# DigitalOutput.net
KiCad netlist of a schematic drawn in Altium Designer
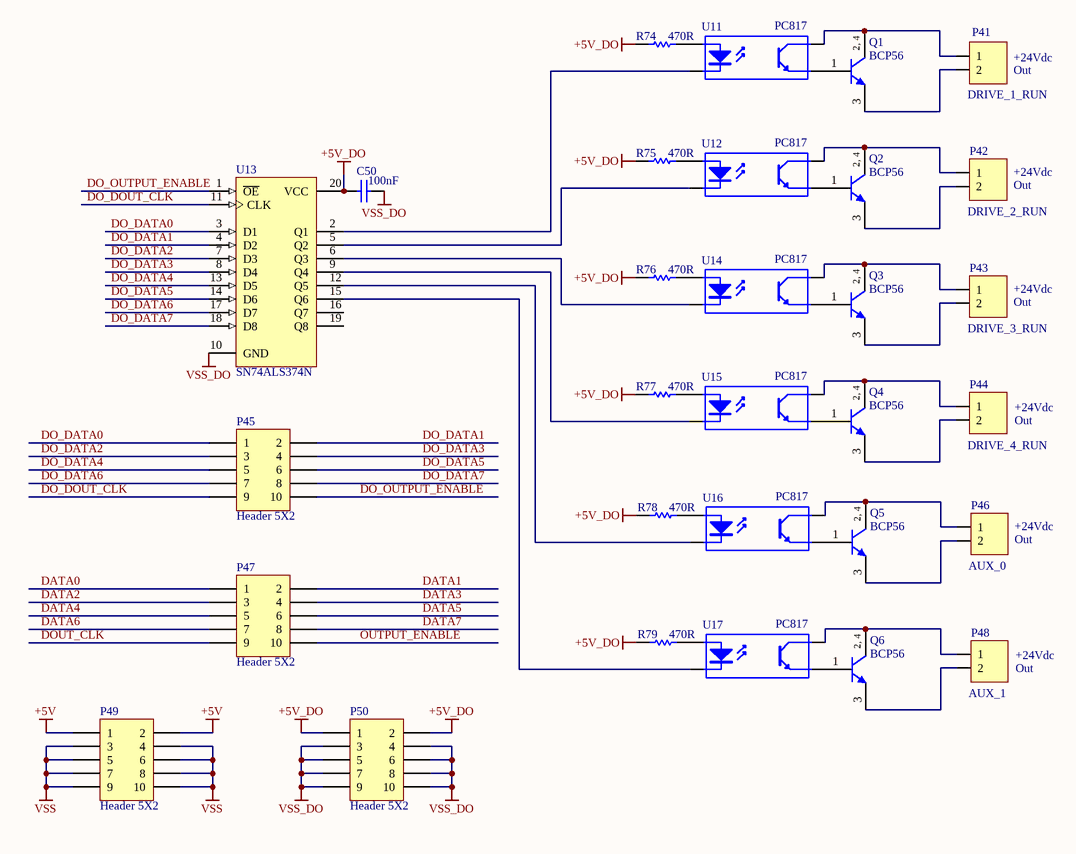
[diagram p0: DigitalOutput.SchDoc]

(export (version "E")
  (design (tool "Eeschema 10.0.6"))
  (components
    (comp (ref "C50")
      (value "100nF")
      (footprint "1206")
      (description "Ceramic Chip Capacitor - Standard")
      (fields (field (name "PUBLISHER") "Altium Limited"))
      (libsource (lib "KEMET Chip Capacitor") (part "C1206"))
    )
    (comp (ref "P41")
      (value "DRIVE_1_RUN")
      (footprint "TERMINAL BLOK 2")
      (description "Terminal blok 2")
      (libsource (lib "") (part "Terminal blok 2 pina_1"))
    )
    (comp (ref "P42")
      (value "DRIVE_2_RUN")
      (footprint "TERMINAL BLOK 2")
      (description "Terminal blok 2")
      (libsource (lib "TERMINAL_CONNECOR_2") (part "Terminal blok 2 pina"))
    )
    (comp (ref "P43")
      (value "DRIVE_3_RUN")
      (footprint "TERMINAL BLOK 2")
      (description "Terminal blok 2")
      (libsource (lib "") (part "Terminal blok 2 pina_2"))
    )
    (comp (ref "P44")
      (value "DRIVE_4_RUN")
      (footprint "TERMINAL BLOK 2")
      (description "Terminal blok 2")
      (libsource (lib "") (part "Terminal blok 2 pina_1"))
    )
    (comp (ref "P45")
      (value "Header 5X2")
      (footprint "HDR2X5")
      (description "Header, 5-Pin, Dual row")
      (fields (field (name "PUBLISHER") "Altium Limited"))
      (libsource (lib "Miscellaneous Connectors") (part "Header 5X2"))
    )
    (comp (ref "P46")
      (value "AUX_0")
      (footprint "TERMINAL BLOK 2")
      (description "Terminal blok 2")
      (libsource (lib "") (part "Terminal blok 2 pina_1"))
    )
    (comp (ref "P47")
      (value "Header 5X2")
      (footprint "HDR2X5")
      (description "Header, 5-Pin, Dual row")
      (fields (field (name "PUBLISHER") "Altium Limited"))
      (libsource (lib "Miscellaneous Connectors") (part "Header 5X2"))
    )
    (comp (ref "P48")
      (value "AUX_1")
      (footprint "TERMINAL BLOK 2")
      (description "Terminal blok 2")
      (libsource (lib "TERMINAL_CONNECOR_2") (part "Terminal blok 2 pina"))
    )
    (comp (ref "P49")
      (value "Header 5X2")
      (footprint "HDR2X5")
      (description "Header, 5-Pin, Dual row")
      (fields (field (name "PUBLISHER") "Altium Limited"))
      (libsource (lib "Miscellaneous Connectors") (part "Header 5X2"))
    )
    (comp (ref "P50")
      (value "Header 5X2")
      (footprint "HDR2X5")
      (description "Header, 5-Pin, Dual row")
      (fields (field (name "PUBLISHER") "Altium Limited"))
      (libsource (lib "Miscellaneous Connectors") (part "Header 5X2"))
    )
    (comp (ref "Q1")
      (value "BCP56")
      (footprint "SOT223_N")
      (description "NPN Medium Power Transistor")
      (fields (field (name "PUBLISHER") "Altium Limited"))
      (libsource (lib "Philips Discrete BJT - Medium Power") (part "BCP56"))
    )
    (comp (ref "Q2")
      (value "BCP56")
      (footprint "SOT223_N")
      (description "NPN Medium Power Transistor")
      (fields (field (name "PUBLISHER") "Altium Limited"))
      (libsource (lib "Philips Discrete BJT - Medium Power") (part "BCP56"))
    )
    (comp (ref "Q3")
      (value "BCP56")
      (footprint "SOT223_N")
      (description "NPN Medium Power Transistor")
      (fields (field (name "PUBLISHER") "Altium Limited"))
      (libsource (lib "Philips Discrete BJT - Medium Power") (part "BCP56"))
    )
    (comp (ref "Q4")
      (value "BCP56")
      (footprint "SOT223_N")
      (description "NPN Medium Power Transistor")
      (fields (field (name "PUBLISHER") "Altium Limited"))
      (libsource (lib "Philips Discrete BJT - Medium Power") (part "BCP56"))
    )
    (comp (ref "Q5")
      (value "BCP56")
      (footprint "SOT223_N")
      (description "NPN Medium Power Transistor")
      (fields (field (name "PUBLISHER") "Altium Limited"))
      (libsource (lib "Philips Discrete BJT - Medium Power") (part "BCP56"))
    )
    (comp (ref "Q6")
      (value "BCP56")
      (footprint "SOT223_N")
      (description "NPN Medium Power Transistor")
      (fields (field (name "PUBLISHER") "Altium Limited"))
      (libsource (lib "Philips Discrete BJT - Medium Power") (part "BCP56"))
    )
    (comp (ref "R74")
      (value "470R")
      (footprint "ERA-0805")
      (fields (field (name "PUBLISHER") "Altium Limited"))
      (libsource (lib "Panasonic Resistor") (part "ERAS"))
    )
    (comp (ref "R75")
      (value "470R")
      (footprint "ERA-0805")
      (fields (field (name "PUBLISHER") "Altium Limited"))
      (libsource (lib "Panasonic Resistor") (part "ERAS"))
    )
    (comp (ref "R76")
      (value "470R")
      (footprint "ERA-0805")
      (fields (field (name "PUBLISHER") "Altium Limited"))
      (libsource (lib "Panasonic Resistor") (part "ERAS"))
    )
    (comp (ref "R77")
      (value "470R")
      (footprint "ERA-0805")
      (fields (field (name "PUBLISHER") "Altium Limited"))
      (libsource (lib "Panasonic Resistor") (part "ERAS"))
    )
    (comp (ref "R78")
      (value "470R")
      (footprint "ERA-0805")
      (fields (field (name "PUBLISHER") "Altium Limited"))
      (libsource (lib "Panasonic Resistor") (part "ERAS"))
    )
    (comp (ref "R79")
      (value "470R")
      (footprint "ERA-0805")
      (fields (field (name "PUBLISHER") "Altium Limited"))
      (libsource (lib "Panasonic Resistor") (part "ERAS"))
    )
    (comp (ref "U11")
      (value "PC817")
      (footprint "DIP-4")
      (description "4-Pin Phototransistor Optocoupler")
      (fields (field (name "PUBLISHER") "Altium Limited"))
      (libsource (lib "Miscellaneous Devices") (part "Optoisolator1"))
    )
    (comp (ref "U12")
      (value "PC817")
      (footprint "DIP-4")
      (description "4-Pin Phototransistor Optocoupler")
      (fields (field (name "PUBLISHER") "Altium Limited"))
      (libsource (lib "Miscellaneous Devices") (part "Optoisolator1"))
    )
    (comp (ref "U13")
      (value "SN74ALS374N")
      (footprint "N020D")
      (description "Octal D-Type Edge-Triggered Flip-Flop with 3-State Outputs")
      (fields (field (name "PUBLISHER") "Altium Limited"))
      (libsource (lib "TI Logic Flip-Flop") (part "SN74ALS374N"))
    )
    (comp (ref "U14")
      (value "PC817")
      (footprint "DIP-4")
      (description "4-Pin Phototransistor Optocoupler")
      (fields (field (name "PUBLISHER") "Altium Limited"))
      (libsource (lib "Miscellaneous Devices") (part "Optoisolator1"))
    )
    (comp (ref "U15")
      (value "PC817")
      (footprint "DIP-4")
      (description "4-Pin Phototransistor Optocoupler")
      (fields (field (name "PUBLISHER") "Altium Limited"))
      (libsource (lib "Miscellaneous Devices") (part "Optoisolator1"))
    )
    (comp (ref "U16")
      (value "PC817")
      (footprint "DIP-4")
      (description "4-Pin Phototransistor Optocoupler")
      (fields (field (name "PUBLISHER") "Altium Limited"))
      (libsource (lib "Miscellaneous Devices") (part "Optoisolator1"))
    )
    (comp (ref "U17")
      (value "PC817")
      (footprint "DIP-4")
      (description "4-Pin Phototransistor Optocoupler")
      (fields (field (name "PUBLISHER") "Altium Limited"))
      (libsource (lib "Miscellaneous Devices") (part "Optoisolator1"))
    )
  )
  (nets
    (net (code "1") (name "+5V") (class "Default")
      (node (ref "P49") (pin "1") (pinfunction "1_1") (pintype "passive"))
      (node (ref "P49") (pin "2") (pinfunction "2_2") (pintype "passive"))
    )
    (net (code "2") (name "+5V_DO") (class "Default")
      (node (ref "C50") (pin "1") (pinfunction "1_1") (pintype "passive"))
      (node (ref "P50") (pin "1") (pinfunction "1_1") (pintype "passive"))
      (node (ref "P50") (pin "2") (pinfunction "2_2") (pintype "passive"))
      (node (ref "R74") (pin "2") (pinfunction "2_2") (pintype "passive"))
      (node (ref "R75") (pin "2") (pinfunction "2_2") (pintype "passive"))
      (node (ref "R76") (pin "2") (pinfunction "2_2") (pintype "passive"))
      (node (ref "R77") (pin "2") (pinfunction "2_2") (pintype "passive"))
      (node (ref "R78") (pin "2") (pinfunction "2_2") (pintype "passive"))
      (node (ref "R79") (pin "2") (pinfunction "2_2") (pintype "passive"))
      (node (ref "U13") (pin "20") (pinfunction "VCC_20") (pintype "power_in"))
    )
    (net (code "3") (name "/DATA0") (class "Default")
      (node (ref "P47") (pin "1") (pinfunction "1_1") (pintype "passive"))
    )
    (net (code "4") (name "/DATA1") (class "Default")
      (node (ref "P47") (pin "2") (pinfunction "2_2") (pintype "passive"))
    )
    (net (code "5") (name "/DATA2") (class "Default")
      (node (ref "P47") (pin "3") (pinfunction "3_3") (pintype "passive"))
    )
    (net (code "6") (name "/DATA3") (class "Default")
      (node (ref "P47") (pin "4") (pinfunction "4_4") (pintype "passive"))
    )
    (net (code "7") (name "/DATA4") (class "Default")
      (node (ref "P47") (pin "5") (pinfunction "5_5") (pintype "passive"))
    )
    (net (code "8") (name "/DATA5") (class "Default")
      (node (ref "P47") (pin "6") (pinfunction "6_6") (pintype "passive"))
    )
    (net (code "9") (name "/DATA6") (class "Default")
      (node (ref "P47") (pin "7") (pinfunction "7_7") (pintype "passive"))
    )
    (net (code "10") (name "/DATA7") (class "Default")
      (node (ref "P47") (pin "8") (pinfunction "8_8") (pintype "passive"))
    )
    (net (code "11") (name "/DOUT_CLK") (class "Default")
      (node (ref "P47") (pin "9") (pinfunction "9_9") (pintype "passive"))
    )
    (net (code "12") (name "/DO_DATA0") (class "Default")
      (node (ref "P45") (pin "1") (pinfunction "1_1") (pintype "passive"))
      (node (ref "U13") (pin "3") (pinfunction "D1_3") (pintype "input"))
    )
    (net (code "13") (name "/DO_DATA1") (class "Default")
      (node (ref "P45") (pin "2") (pinfunction "2_2") (pintype "passive"))
      (node (ref "U13") (pin "4") (pinfunction "D2_4") (pintype "input"))
    )
    (net (code "14") (name "/DO_DATA2") (class "Default")
      (node (ref "P45") (pin "3") (pinfunction "3_3") (pintype "passive"))
      (node (ref "U13") (pin "7") (pinfunction "D3_7") (pintype "input"))
    )
    (net (code "15") (name "/DO_DATA3") (class "Default")
      (node (ref "P45") (pin "4") (pinfunction "4_4") (pintype "passive"))
      (node (ref "U13") (pin "8") (pinfunction "D4_8") (pintype "input"))
    )
    (net (code "16") (name "/DO_DATA4") (class "Default")
      (node (ref "P45") (pin "5") (pinfunction "5_5") (pintype "passive"))
      (node (ref "U13") (pin "13") (pinfunction "D5_13") (pintype "input"))
    )
    (net (code "17") (name "/DO_DATA5") (class "Default")
      (node (ref "P45") (pin "6") (pinfunction "6_6") (pintype "passive"))
      (node (ref "U13") (pin "14") (pinfunction "D6_14") (pintype "input"))
    )
    (net (code "18") (name "/DO_DATA6") (class "Default")
      (node (ref "P45") (pin "7") (pinfunction "7_7") (pintype "passive"))
      (node (ref "U13") (pin "17") (pinfunction "D7_17") (pintype "input"))
    )
    (net (code "19") (name "/DO_DATA7") (class "Default")
      (node (ref "P45") (pin "8") (pinfunction "8_8") (pintype "passive"))
      (node (ref "U13") (pin "18") (pinfunction "D8_18") (pintype "input"))
    )
    (net (code "20") (name "/DO_DOUT_CLK") (class "Default")
      (node (ref "P45") (pin "9") (pinfunction "9_9") (pintype "passive"))
      (node (ref "U13") (pin "11") (pinfunction "CLK_11") (pintype "input"))
    )
    (net (code "21") (name "/DO_OUTPUT_ENABLE") (class "Default")
      (node (ref "P45") (pin "10") (pinfunction "10_10") (pintype "passive"))
      (node (ref "U13") (pin "1") (pinfunction "~{OE}_1") (pintype "input"))
    )
    (net (code "22") (name "/OUTPUT_ENABLE") (class "Default")
      (node (ref "P47") (pin "10") (pinfunction "10_10") (pintype "passive"))
    )
    (net (code "23") (name "Net-(Q1-B)") (class "Default")
      (node (ref "Q1") (pin "1") (pinfunction "B_1") (pintype "passive"))
      (node (ref "U11") (pin "3") (pinfunction "E_3") (pintype "passive"))
    )
    (net (code "24") (name "Net-(Q1-E)") (class "Default")
      (node (ref "P41") (pin "2") (pinfunction "2_2") (pintype "passive"))
      (node (ref "Q1") (pin "3") (pinfunction "E_3") (pintype "passive"))
    )
    (net (code "25") (name "Net-(Q2-B)") (class "Default")
      (node (ref "Q2") (pin "1") (pinfunction "B_1") (pintype "passive"))
      (node (ref "U12") (pin "3") (pinfunction "E_3") (pintype "passive"))
    )
    (net (code "26") (name "Net-(Q2-E)") (class "Default")
      (node (ref "P42") (pin "2") (pinfunction "2_2") (pintype "passive"))
      (node (ref "Q2") (pin "3") (pinfunction "E_3") (pintype "passive"))
    )
    (net (code "27") (name "Net-(Q3-B)") (class "Default")
      (node (ref "Q3") (pin "1") (pinfunction "B_1") (pintype "passive"))
      (node (ref "U14") (pin "3") (pinfunction "E_3") (pintype "passive"))
    )
    (net (code "28") (name "Net-(Q3-E)") (class "Default")
      (node (ref "P43") (pin "2") (pinfunction "2_2") (pintype "passive"))
      (node (ref "Q3") (pin "3") (pinfunction "E_3") (pintype "passive"))
    )
    (net (code "29") (name "Net-(Q4-B)") (class "Default")
      (node (ref "Q4") (pin "1") (pinfunction "B_1") (pintype "passive"))
      (node (ref "U15") (pin "3") (pinfunction "E_3") (pintype "passive"))
    )
    (net (code "30") (name "Net-(Q4-E)") (class "Default")
      (node (ref "P44") (pin "2") (pinfunction "2_2") (pintype "passive"))
      (node (ref "Q4") (pin "3") (pinfunction "E_3") (pintype "passive"))
    )
    (net (code "31") (name "Net-(Q5-B)") (class "Default")
      (node (ref "Q5") (pin "1") (pinfunction "B_1") (pintype "passive"))
      (node (ref "U16") (pin "3") (pinfunction "E_3") (pintype "passive"))
    )
    (net (code "32") (name "Net-(Q5-E)") (class "Default")
      (node (ref "P46") (pin "2") (pinfunction "2_2") (pintype "passive"))
      (node (ref "Q5") (pin "3") (pinfunction "E_3") (pintype "passive"))
    )
    (net (code "33") (name "Net-(Q6-B)") (class "Default")
      (node (ref "Q6") (pin "1") (pinfunction "B_1") (pintype "passive"))
      (node (ref "U17") (pin "3") (pinfunction "E_3") (pintype "passive"))
    )
    (net (code "34") (name "Net-(Q6-E)") (class "Default")
      (node (ref "P48") (pin "2") (pinfunction "2_2") (pintype "passive"))
      (node (ref "Q6") (pin "3") (pinfunction "E_3") (pintype "passive"))
    )
    (net (code "35") (name "Net-(U11-A)") (class "Default")
      (node (ref "R74") (pin "1") (pinfunction "1_1") (pintype "passive"))
      (node (ref "U11") (pin "1") (pinfunction "A_1") (pintype "passive"))
    )
    (net (code "36") (name "Net-(U11-C)") (class "Default")
      (node (ref "P41") (pin "1") (pinfunction "1_1") (pintype "passive"))
      (node (ref "Q1") (pin "2") (pinfunction "C_2") (pintype "passive"))
      (node (ref "Q1") (pin "4") (pinfunction "C_4") (pintype "passive"))
      (node (ref "U11") (pin "4") (pinfunction "C_4") (pintype "passive"))
    )
    (net (code "37") (name "Net-(U11-K)") (class "Default")
      (node (ref "U11") (pin "2") (pinfunction "K_2") (pintype "passive"))
      (node (ref "U13") (pin "2") (pinfunction "Q1_2") (pintype "tri_state"))
    )
    (net (code "38") (name "Net-(U12-A)") (class "Default")
      (node (ref "R75") (pin "1") (pinfunction "1_1") (pintype "passive"))
      (node (ref "U12") (pin "1") (pinfunction "A_1") (pintype "passive"))
    )
    (net (code "39") (name "Net-(U12-C)") (class "Default")
      (node (ref "P42") (pin "1") (pinfunction "1_1") (pintype "passive"))
      (node (ref "Q2") (pin "2") (pinfunction "C_2") (pintype "passive"))
      (node (ref "Q2") (pin "4") (pinfunction "C_4") (pintype "passive"))
      (node (ref "U12") (pin "4") (pinfunction "C_4") (pintype "passive"))
    )
    (net (code "40") (name "Net-(U12-K)") (class "Default")
      (node (ref "U12") (pin "2") (pinfunction "K_2") (pintype "passive"))
      (node (ref "U13") (pin "5") (pinfunction "Q2_5") (pintype "tri_state"))
    )
    (net (code "41") (name "Net-(U13-Q3)") (class "Default")
      (node (ref "U13") (pin "6") (pinfunction "Q3_6") (pintype "tri_state"))
      (node (ref "U14") (pin "2") (pinfunction "K_2") (pintype "passive"))
    )
    (net (code "42") (name "Net-(U13-Q4)") (class "Default")
      (node (ref "U13") (pin "9") (pinfunction "Q4_9") (pintype "tri_state"))
      (node (ref "U15") (pin "2") (pinfunction "K_2") (pintype "passive"))
    )
    (net (code "43") (name "Net-(U13-Q5)") (class "Default")
      (node (ref "U13") (pin "12") (pinfunction "Q5_12") (pintype "tri_state"))
      (node (ref "U16") (pin "2") (pinfunction "K_2") (pintype "passive"))
    )
    (net (code "44") (name "Net-(U13-Q6)") (class "Default")
      (node (ref "U13") (pin "15") (pinfunction "Q6_15") (pintype "tri_state"))
      (node (ref "U17") (pin "2") (pinfunction "K_2") (pintype "passive"))
    )
    (net (code "45") (name "Net-(U14-A)") (class "Default")
      (node (ref "R76") (pin "1") (pinfunction "1_1") (pintype "passive"))
      (node (ref "U14") (pin "1") (pinfunction "A_1") (pintype "passive"))
    )
    (net (code "46") (name "Net-(U14-C)") (class "Default")
      (node (ref "P43") (pin "1") (pinfunction "1_1") (pintype "passive"))
      (node (ref "Q3") (pin "2") (pinfunction "C_2") (pintype "passive"))
      (node (ref "Q3") (pin "4") (pinfunction "C_4") (pintype "passive"))
      (node (ref "U14") (pin "4") (pinfunction "C_4") (pintype "passive"))
    )
    (net (code "47") (name "Net-(U15-A)") (class "Default")
      (node (ref "R77") (pin "1") (pinfunction "1_1") (pintype "passive"))
      (node (ref "U15") (pin "1") (pinfunction "A_1") (pintype "passive"))
    )
    (net (code "48") (name "Net-(U15-C)") (class "Default")
      (node (ref "P44") (pin "1") (pinfunction "1_1") (pintype "passive"))
      (node (ref "Q4") (pin "2") (pinfunction "C_2") (pintype "passive"))
      (node (ref "Q4") (pin "4") (pinfunction "C_4") (pintype "passive"))
      (node (ref "U15") (pin "4") (pinfunction "C_4") (pintype "passive"))
    )
    (net (code "49") (name "Net-(U16-A)") (class "Default")
      (node (ref "R78") (pin "1") (pinfunction "1_1") (pintype "passive"))
      (node (ref "U16") (pin "1") (pinfunction "A_1") (pintype "passive"))
    )
    (net (code "50") (name "Net-(U16-C)") (class "Default")
      (node (ref "P46") (pin "1") (pinfunction "1_1") (pintype "passive"))
      (node (ref "Q5") (pin "2") (pinfunction "C_2") (pintype "passive"))
      (node (ref "Q5") (pin "4") (pinfunction "C_4") (pintype "passive"))
      (node (ref "U16") (pin "4") (pinfunction "C_4") (pintype "passive"))
    )
    (net (code "51") (name "Net-(U17-A)") (class "Default")
      (node (ref "R79") (pin "1") (pinfunction "1_1") (pintype "passive"))
      (node (ref "U17") (pin "1") (pinfunction "A_1") (pintype "passive"))
    )
    (net (code "52") (name "Net-(U17-C)") (class "Default")
      (node (ref "P48") (pin "1") (pinfunction "1_1") (pintype "passive"))
      (node (ref "Q6") (pin "2") (pinfunction "C_2") (pintype "passive"))
      (node (ref "Q6") (pin "4") (pinfunction "C_4") (pintype "passive"))
      (node (ref "U17") (pin "4") (pinfunction "C_4") (pintype "passive"))
    )
    (net (code "53") (name "VSS") (class "Default")
      (node (ref "P49") (pin "10") (pinfunction "10_10") (pintype "passive"))
      (node (ref "P49") (pin "3") (pinfunction "3_3") (pintype "passive"))
      (node (ref "P49") (pin "4") (pinfunction "4_4") (pintype "passive"))
      (node (ref "P49") (pin "5") (pinfunction "5_5") (pintype "passive"))
      (node (ref "P49") (pin "6") (pinfunction "6_6") (pintype "passive"))
      (node (ref "P49") (pin "7") (pinfunction "7_7") (pintype "passive"))
      (node (ref "P49") (pin "8") (pinfunction "8_8") (pintype "passive"))
      (node (ref "P49") (pin "9") (pinfunction "9_9") (pintype "passive"))
    )
    (net (code "54") (name "VSS_DO") (class "Default")
      (node (ref "C50") (pin "2") (pinfunction "2_2") (pintype "passive"))
      (node (ref "P50") (pin "10") (pinfunction "10_10") (pintype "passive"))
      (node (ref "P50") (pin "3") (pinfunction "3_3") (pintype "passive"))
      (node (ref "P50") (pin "4") (pinfunction "4_4") (pintype "passive"))
      (node (ref "P50") (pin "5") (pinfunction "5_5") (pintype "passive"))
      (node (ref "P50") (pin "6") (pinfunction "6_6") (pintype "passive"))
      (node (ref "P50") (pin "7") (pinfunction "7_7") (pintype "passive"))
      (node (ref "P50") (pin "8") (pinfunction "8_8") (pintype "passive"))
      (node (ref "P50") (pin "9") (pinfunction "9_9") (pintype "passive"))
      (node (ref "U13") (pin "10") (pinfunction "GND_10") (pintype "power_in"))
    )
    (net (code "55") (name "unconnected-(U13-Q7-Pad16)") (class "Default")
      (node (ref "U13") (pin "16") (pinfunction "Q7_16") (pintype "tri_state"))
    )
    (net (code "56") (name "unconnected-(U13-Q8-Pad19)") (class "Default")
      (node (ref "U13") (pin "19") (pinfunction "Q8_19") (pintype "tri_state"))
    )
  )
)
